# untitled.net
KiCad netlist of a schematic drawn in EAGLE
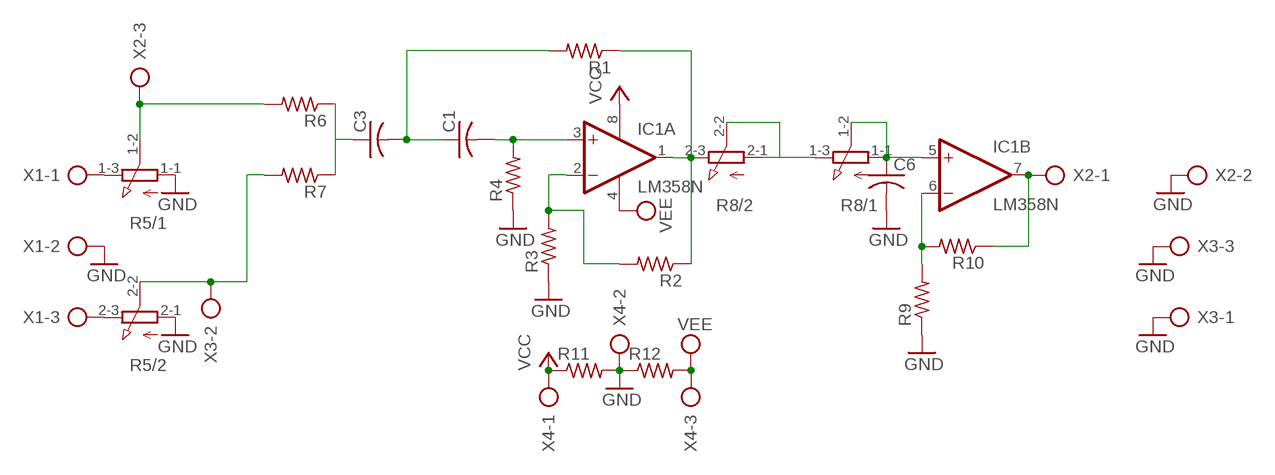
[diagram p0: schematic, sheet 1]

(export (version "E")
  (design (tool "Eeschema 10.0.6"))
  (components
    (comp (ref "C1")
      (value "C-US025-025X050")
      (footprint "eagle-import:C025-025X050")
      (libsource (lib "eagle-import") (part "C-US025-025X050"))
    )
    (comp (ref "C3")
      (value "C-US025-025X050")
      (footprint "eagle-import:C025-025X050")
      (libsource (lib "eagle-import") (part "C-US025-025X050"))
    )
    (comp (ref "C6")
      (value "C-US025-025X050")
      (footprint "eagle-import:C025-025X050")
      (libsource (lib "eagle-import") (part "C-US025-025X050"))
    )
    (comp (ref "IC1")
      (value "LM358N")
      (footprint "eagle-import:DIL08")
      (libsource (lib "eagle-import") (part "LM358N"))
    )
    (comp (ref "R1")
      (value "FLIPFLOP-RES")
      (footprint "eagle-import:0805-THM")
      (libsource (lib "eagle-import") (part "FLIPFLOP-RES"))
    )
    (comp (ref "R2")
      (value "FLIPFLOP-RES")
      (footprint "eagle-import:0805-THM")
      (libsource (lib "eagle-import") (part "FLIPFLOP-RES"))
    )
    (comp (ref "R3")
      (value "FLIPFLOP-RES")
      (footprint "eagle-import:0805-THM")
      (libsource (lib "eagle-import") (part "FLIPFLOP-RES"))
    )
    (comp (ref "R4")
      (value "FLIPFLOP-RES")
      (footprint "eagle-import:0805-THM")
      (libsource (lib "eagle-import") (part "FLIPFLOP-RES"))
    )
    (comp (ref "R5")
      (value "3RP/1610G")
      (footprint "eagle-import:3RP_1610G")
      (libsource (lib "eagle-import") (part "3RP/1610G"))
    )
    (comp (ref "R6")
      (value "FLIPFLOP-RES")
      (footprint "eagle-import:0805-THM")
      (libsource (lib "eagle-import") (part "FLIPFLOP-RES"))
    )
    (comp (ref "R7")
      (value "FLIPFLOP-RES")
      (footprint "eagle-import:0805-THM")
      (libsource (lib "eagle-import") (part "FLIPFLOP-RES"))
    )
    (comp (ref "R8")
      (value "3RP/1610G")
      (footprint "eagle-import:3RP_1610G")
      (libsource (lib "eagle-import") (part "3RP/1610G"))
    )
    (comp (ref "R9")
      (value "FLIPFLOP-RES")
      (footprint "eagle-import:0805-THM")
      (libsource (lib "eagle-import") (part "FLIPFLOP-RES"))
    )
    (comp (ref "R10")
      (value "FLIPFLOP-RES")
      (footprint "eagle-import:0805-THM")
      (libsource (lib "eagle-import") (part "FLIPFLOP-RES"))
    )
    (comp (ref "R11")
      (value "R-US_0309/10")
      (footprint "eagle-import:0309_10")
      (libsource (lib "eagle-import") (part "R-US_0309/10"))
    )
    (comp (ref "R12")
      (value "R-US_0309/10")
      (footprint "eagle-import:0309_10")
      (libsource (lib "eagle-import") (part "R-US_0309/10"))
    )
    (comp (ref "X1")
      (value "AK300/3")
      (footprint "eagle-import:AK300_3")
      (libsource (lib "eagle-import") (part "AK300/3"))
    )
    (comp (ref "X2")
      (value "AK300/3")
      (footprint "eagle-import:AK300_3")
      (libsource (lib "eagle-import") (part "AK300/3"))
    )
    (comp (ref "X3")
      (value "AK300/3")
      (footprint "eagle-import:AK300_3")
      (libsource (lib "eagle-import") (part "AK300/3"))
    )
    (comp (ref "X4")
      (value "AK300/3")
      (footprint "eagle-import:AK300_3")
      (libsource (lib "eagle-import") (part "AK300/3"))
    )
  )
  (nets
    (net (code "1") (name "GND") (class "Default")
      (node (ref "C6") (pin "2") (pinfunction "2_2") (pintype "passive"))
      (node (ref "R11") (pin "2") (pinfunction "2_2") (pintype "passive"))
      (node (ref "R12") (pin "1") (pinfunction "1_1") (pintype "passive"))
      (node (ref "R3") (pin "1") (pinfunction "1_1") (pintype "passive"))
      (node (ref "R4") (pin "1") (pinfunction "1_1") (pintype "passive"))
      (node (ref "R5") (pin "1-1") (pinfunction "A_1-1") (pintype "passive"))
      (node (ref "R5") (pin "2-1") (pinfunction "A_2-1") (pintype "passive"))
      (node (ref "R9") (pin "1") (pinfunction "1_1") (pintype "passive"))
      (node (ref "X1") (pin "2") (pinfunction "KL_2") (pintype "passive"))
      (node (ref "X2") (pin "2") (pinfunction "KL_2") (pintype "passive"))
      (node (ref "X3") (pin "1") (pinfunction "KL_1") (pintype "passive"))
      (node (ref "X3") (pin "3") (pinfunction "KL_3") (pintype "passive"))
      (node (ref "X4") (pin "2") (pinfunction "KL_2") (pintype "passive"))
    )
    (net (code "2") (name "Net-(C1-Pad1)") (class "Default")
      (node (ref "C1") (pin "1") (pinfunction "1_1") (pintype "passive"))
      (node (ref "C3") (pin "2") (pinfunction "2_2") (pintype "passive"))
      (node (ref "R1") (pin "2") (pinfunction "2_2") (pintype "passive"))
    )
    (net (code "3") (name "Net-(C3-Pad1)") (class "Default")
      (node (ref "C3") (pin "1") (pinfunction "1_1") (pintype "passive"))
      (node (ref "R6") (pin "1") (pinfunction "1_1") (pintype "passive"))
      (node (ref "R7") (pin "1") (pinfunction "1_1") (pintype "passive"))
    )
    (net (code "4") (name "Net-(IC1A-+IN)") (class "Default")
      (node (ref "C1") (pin "2") (pinfunction "2_2") (pintype "passive"))
      (node (ref "IC1") (pin "3") (pinfunction "+IN_3") (pintype "input"))
      (node (ref "R4") (pin "2") (pinfunction "2_2") (pintype "passive"))
    )
    (net (code "5") (name "Net-(IC1A--IN)") (class "Default")
      (node (ref "IC1") (pin "2") (pinfunction "-IN_2") (pintype "input"))
      (node (ref "R2") (pin "2") (pinfunction "2_2") (pintype "passive"))
      (node (ref "R3") (pin "2") (pinfunction "2_2") (pintype "passive"))
    )
    (net (code "6") (name "Net-(IC1A-OUT)") (class "Default")
      (node (ref "IC1") (pin "1") (pinfunction "OUT_1") (pintype "output"))
      (node (ref "R1") (pin "1") (pinfunction "1_1") (pintype "passive"))
      (node (ref "R2") (pin "1") (pinfunction "1_1") (pintype "passive"))
      (node (ref "R8") (pin "2-3") (pinfunction "E_2-3") (pintype "passive"))
    )
    (net (code "7") (name "Net-(IC1B-+IN)") (class "Default")
      (node (ref "C6") (pin "1") (pinfunction "1_1") (pintype "passive"))
      (node (ref "IC1") (pin "5") (pinfunction "+IN_5") (pintype "input"))
      (node (ref "R8") (pin "1-1") (pinfunction "A_1-1") (pintype "passive"))
      (node (ref "R8") (pin "1-2") (pinfunction "S_1-2") (pintype "passive"))
    )
    (net (code "8") (name "Net-(IC1B--IN)") (class "Default")
      (node (ref "IC1") (pin "6") (pinfunction "-IN_6") (pintype "input"))
      (node (ref "R10") (pin "2") (pinfunction "2_2") (pintype "passive"))
      (node (ref "R9") (pin "2") (pinfunction "2_2") (pintype "passive"))
    )
    (net (code "9") (name "Net-(IC1B-OUT)") (class "Default")
      (node (ref "IC1") (pin "7") (pinfunction "OUT_7") (pintype "output"))
      (node (ref "R10") (pin "1") (pinfunction "1_1") (pintype "passive"))
      (node (ref "X2") (pin "1") (pinfunction "KL_1") (pintype "passive"))
    )
    (net (code "10") (name "Net-(R5A-E)") (class "Default")
      (node (ref "R5") (pin "1-3") (pinfunction "E_1-3") (pintype "passive"))
      (node (ref "X1") (pin "1") (pinfunction "KL_1") (pintype "passive"))
    )
    (net (code "11") (name "Net-(R5A-S)") (class "Default")
      (node (ref "R5") (pin "1-2") (pinfunction "S_1-2") (pintype "passive"))
      (node (ref "R6") (pin "2") (pinfunction "2_2") (pintype "passive"))
      (node (ref "X2") (pin "3") (pinfunction "KL_3") (pintype "passive"))
    )
    (net (code "12") (name "Net-(R5B-E)") (class "Default")
      (node (ref "R5") (pin "2-3") (pinfunction "E_2-3") (pintype "passive"))
      (node (ref "X1") (pin "3") (pinfunction "KL_3") (pintype "passive"))
    )
    (net (code "13") (name "Net-(R5B-S)") (class "Default")
      (node (ref "R5") (pin "2-2") (pinfunction "S_2-2") (pintype "passive"))
      (node (ref "R7") (pin "2") (pinfunction "2_2") (pintype "passive"))
      (node (ref "X3") (pin "2") (pinfunction "KL_2") (pintype "passive"))
    )
    (net (code "14") (name "Net-(R8A-E)") (class "Default")
      (node (ref "R8") (pin "1-3") (pinfunction "E_1-3") (pintype "passive"))
      (node (ref "R8") (pin "2-1") (pinfunction "A_2-1") (pintype "passive"))
      (node (ref "R8") (pin "2-2") (pinfunction "S_2-2") (pintype "passive"))
    )
    (net (code "15") (name "VCC") (class "Default")
      (node (ref "IC1") (pin "8") (pinfunction "V+_8") (pintype "power_in"))
      (node (ref "R11") (pin "1") (pinfunction "1_1") (pintype "passive"))
      (node (ref "X4") (pin "1") (pinfunction "KL_1") (pintype "passive"))
    )
    (net (code "16") (name "VEE") (class "Default")
      (node (ref "IC1") (pin "4") (pinfunction "V-_4") (pintype "power_in"))
      (node (ref "R12") (pin "2") (pinfunction "2_2") (pintype "passive"))
      (node (ref "X4") (pin "3") (pinfunction "KL_3") (pintype "passive"))
    )
  )
)
